# BM83.net
KiCad netlist of a schematic drawn in Altium Designer
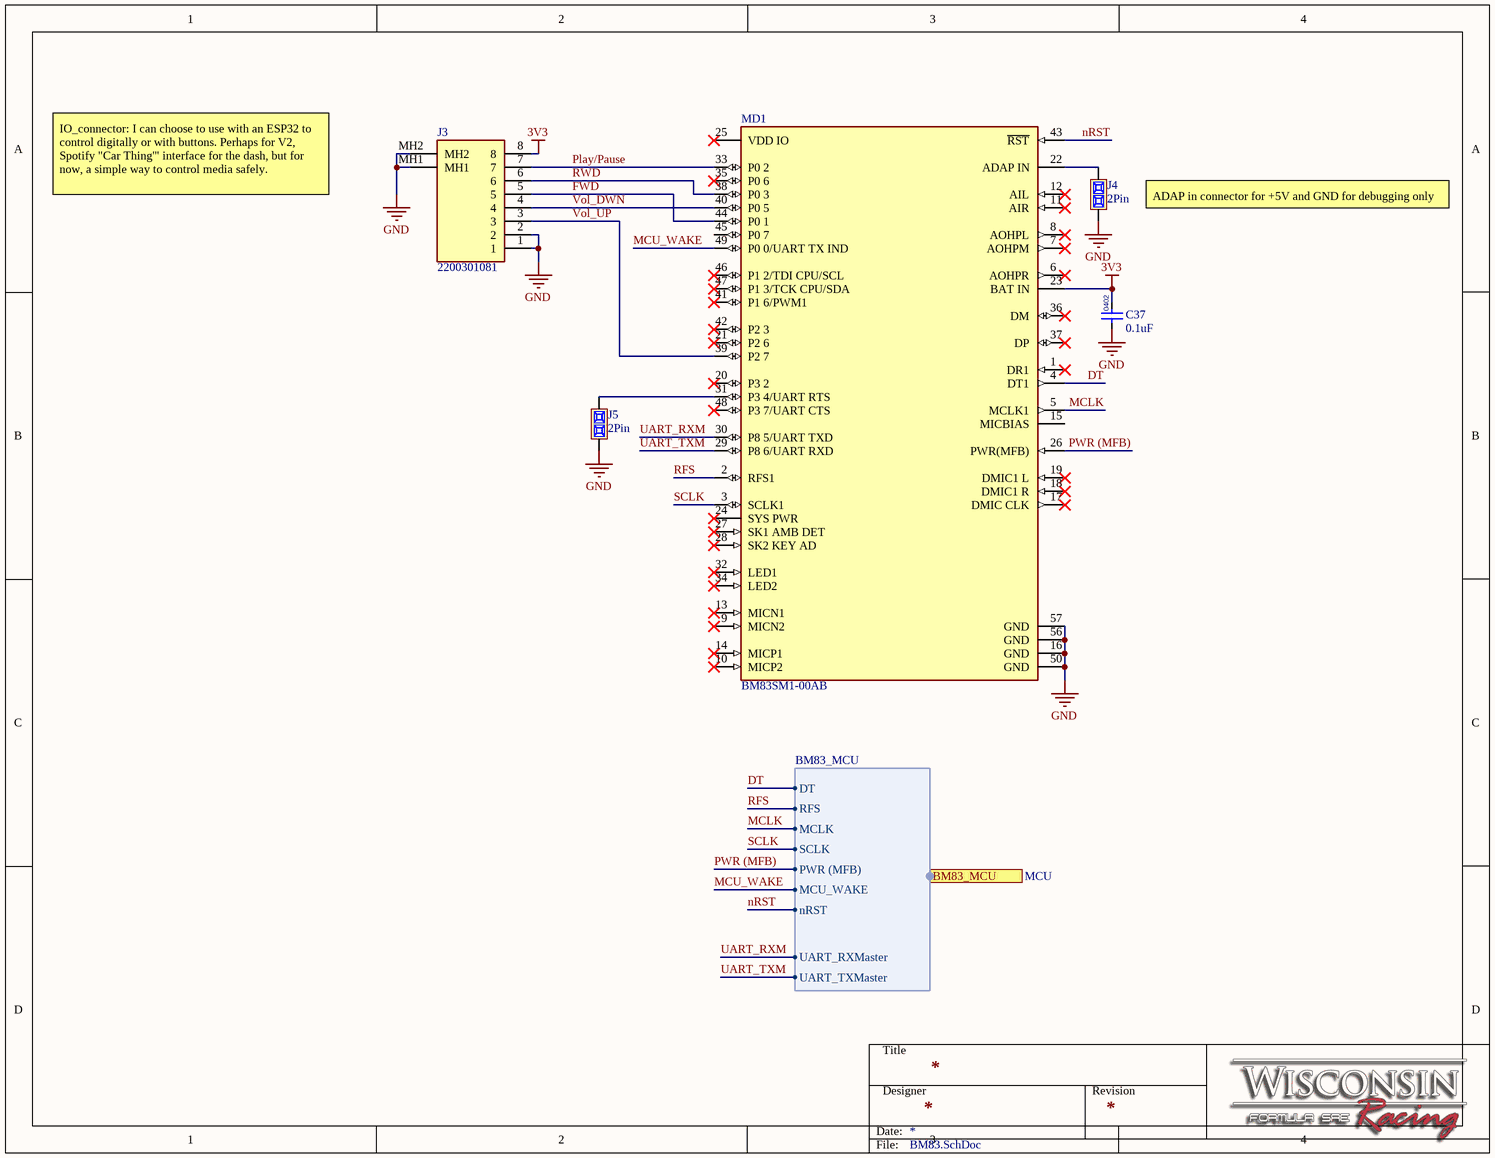
[diagram p0: BM83.SchDoc]

(export (version "E")
  (design (tool "Eeschema 10.0.6"))
  (components
    (comp (ref "C37")
      (value "0.1uF")
      (footprint "FP-CC0402-IPC_B")
      (fields (field (name "TOLERANCE") "10%"))
      (libsource (lib "University of Wisconsin Formula FSAE") (part "0402 ceramic cap"))
    )
    (comp (ref "J3")
      (value "2200301081")
      (footprint "SamacSys:2200301081")
      (description "Connector")
      (libsource (lib "*") (part "2200301081"))
    )
    (comp (ref "J4")
      (value "2Pin")
      (footprint "2 Pin Male")
      (libsource (lib "University of Wisconsin Formula FSAE") (part "2 Pin Male"))
    )
    (comp (ref "J5")
      (value "2Pin")
      (footprint "2 Pin Male")
      (libsource (lib "University of Wisconsin Formula FSAE") (part "2 Pin Male"))
    )
    (comp (ref "MD1")
      (value "BM83SM1-00AB")
      (footprint "FP-BM83SM1-00AB-MFG")
      (description "BLUETOOTH AUDIO MODULE")
      (libsource (lib "Altium Content Vault") (part "59273137af04f48cb9dd2df4763d70c"))
    )
  )
  (nets
    (net (code "2") (name "/DT") (class "Default")
      (node (ref "MD1") (pin "4") (pinfunction "DT1_4") (pintype "output"))
    )
    (net (code "3") (name "/FWD") (class "Default")
      (node (ref "J3") (pin "5") (pinfunction "5_5") (pintype "passive"))
      (node (ref "MD1") (pin "44") (pinfunction "P0_1_44") (pintype "bidirectional"))
    )
    (net (code "4") (name "/MCLK") (class "Default")
      (node (ref "MD1") (pin "5") (pinfunction "MCLK1_5") (pintype "output"))
    )
    (net (code "5") (name "/MCU_WAKE") (class "Default")
      (node (ref "MD1") (pin "49") (pinfunction "P0_0/UART_TX_IND_49") (pintype "bidirectional"))
    )
    (net (code "6") (name "/PWR (MFB)") (class "Default")
      (node (ref "MD1") (pin "26") (pinfunction "PWR(MFB)_26") (pintype "input"))
    )
    (net (code "7") (name "/Play{slash}Pause") (class "Default")
      (node (ref "J3") (pin "7") (pinfunction "7_7") (pintype "passive"))
      (node (ref "MD1") (pin "33") (pinfunction "P0_2_33") (pintype "bidirectional"))
    )
    (net (code "8") (name "/RFS") (class "Default")
      (node (ref "MD1") (pin "2") (pinfunction "RFS1_2") (pintype "bidirectional"))
    )
    (net (code "9") (name "/RWD") (class "Default")
      (node (ref "J3") (pin "6") (pinfunction "6_6") (pintype "passive"))
      (node (ref "MD1") (pin "38") (pinfunction "P0_3_38") (pintype "bidirectional"))
    )
    (net (code "10") (name "/SCLK") (class "Default")
      (node (ref "MD1") (pin "3") (pinfunction "SCLK1_3") (pintype "bidirectional"))
    )
    (net (code "11") (name "/UART_RXM") (class "Default")
      (node (ref "MD1") (pin "30") (pinfunction "P8_5/UART_TXD_30") (pintype "bidirectional"))
    )
    (net (code "12") (name "/UART_TXM") (class "Default")
      (node (ref "MD1") (pin "29") (pinfunction "P8_6/UART_RXD_29") (pintype "bidirectional"))
    )
    (net (code "13") (name "/Vol_DWN") (class "Default")
      (node (ref "J3") (pin "4") (pinfunction "4_4") (pintype "passive"))
      (node (ref "MD1") (pin "40") (pinfunction "P0_5_40") (pintype "bidirectional"))
    )
    (net (code "14") (name "/Vol_UP") (class "Default")
      (node (ref "J3") (pin "3") (pinfunction "3_3") (pintype "passive"))
      (node (ref "MD1") (pin "39") (pinfunction "P2_7_39") (pintype "bidirectional"))
    )
    (net (code "15") (name "/nRST") (class "Default")
      (node (ref "MD1") (pin "43") (pinfunction "~{RST}_43") (pintype "input"))
    )
    (net (code "17") (name "3V3") (class "Default")
      (node (ref "C37") (pin "2") (pinfunction "2_2") (pintype "passive"))
      (node (ref "J3") (pin "8") (pinfunction "8_8") (pintype "passive"))
      (node (ref "MD1") (pin "23") (pinfunction "BAT_IN_23") (pintype "power_in"))
    )
    (net (code "18") (name "GND") (class "Default")
      (node (ref "C37") (pin "1") (pinfunction "1_1") (pintype "passive"))
      (node (ref "J3") (pin "1") (pinfunction "1_1") (pintype "passive"))
      (node (ref "J3") (pin "2") (pinfunction "2_2") (pintype "passive"))
      (node (ref "J3") (pin "MH1") (pinfunction "MH1_MH1") (pintype "passive"))
      (node (ref "J3") (pin "MH2") (pinfunction "MH2_MH2") (pintype "passive"))
      (node (ref "J4") (pin "1") (pinfunction "1_1") (pintype "passive"))
      (node (ref "J5") (pin "1") (pinfunction "1_1") (pintype "passive"))
      (node (ref "MD1") (pin "16") (pinfunction "GND_16") (pintype "power_in"))
      (node (ref "MD1") (pin "50") (pinfunction "GND_50") (pintype "power_in"))
      (node (ref "MD1") (pin "56") (pinfunction "GND_56") (pintype "power_in"))
      (node (ref "MD1") (pin "57") (pinfunction "GND_57") (pintype "power_in"))
    )
    (net (code "19") (name "Net-(MD1-ADAP_IN)") (class "Default")
      (node (ref "J4") (pin "2") (pinfunction "2_2") (pintype "passive"))
      (node (ref "MD1") (pin "22") (pinfunction "ADAP_IN_22") (pintype "power_in"))
    )
    (net (code "20") (name "Net-(MD1-P3_4{slash}UART_RTS)") (class "Default")
      (node (ref "J5") (pin "2") (pinfunction "2_2") (pintype "passive"))
      (node (ref "MD1") (pin "31") (pinfunction "P3_4/UART_RTS_31") (pintype "bidirectional"))
    )
    (net (code "21") (name "unconnected-(MD1-AIL-Pad12)") (class "Default")
      (node (ref "MD1") (pin "12") (pinfunction "AIL_12") (pintype "input+no_connect"))
    )
    (net (code "22") (name "unconnected-(MD1-AIR-Pad11)") (class "Default")
      (node (ref "MD1") (pin "11") (pinfunction "AIR_11") (pintype "input+no_connect"))
    )
    (net (code "23") (name "unconnected-(MD1-AOHPL-Pad8)") (class "Default")
      (node (ref "MD1") (pin "8") (pinfunction "AOHPL_8") (pintype "output+no_connect"))
    )
    (net (code "24") (name "unconnected-(MD1-AOHPM-Pad7)") (class "Default")
      (node (ref "MD1") (pin "7") (pinfunction "AOHPM_7") (pintype "output+no_connect"))
    )
    (net (code "25") (name "unconnected-(MD1-AOHPR-Pad6)") (class "Default")
      (node (ref "MD1") (pin "6") (pinfunction "AOHPR_6") (pintype "output+no_connect"))
    )
    (net (code "26") (name "unconnected-(MD1-DM-Pad36)") (class "Default")
      (node (ref "MD1") (pin "36") (pinfunction "DM_36") (pintype "bidirectional+no_connect"))
    )
    (net (code "27") (name "unconnected-(MD1-DMIC1_L-Pad19)") (class "Default")
      (node (ref "MD1") (pin "19") (pinfunction "DMIC1_L_19") (pintype "input+no_connect"))
    )
    (net (code "28") (name "unconnected-(MD1-DMIC1_R-Pad18)") (class "Default")
      (node (ref "MD1") (pin "18") (pinfunction "DMIC1_R_18") (pintype "input+no_connect"))
    )
    (net (code "29") (name "unconnected-(MD1-DMIC_CLK-Pad17)") (class "Default")
      (node (ref "MD1") (pin "17") (pinfunction "DMIC_CLK_17") (pintype "output+no_connect"))
    )
    (net (code "30") (name "unconnected-(MD1-DP-Pad37)") (class "Default")
      (node (ref "MD1") (pin "37") (pinfunction "DP_37") (pintype "bidirectional+no_connect"))
    )
    (net (code "31") (name "unconnected-(MD1-DR1-Pad1)") (class "Default")
      (node (ref "MD1") (pin "1") (pinfunction "DR1_1") (pintype "input+no_connect"))
    )
    (net (code "32") (name "unconnected-(MD1-LED1-Pad32)") (class "Default")
      (node (ref "MD1") (pin "32") (pinfunction "LED1_32") (pintype "input+no_connect"))
    )
    (net (code "33") (name "unconnected-(MD1-LED2-Pad34)") (class "Default")
      (node (ref "MD1") (pin "34") (pinfunction "LED2_34") (pintype "input+no_connect"))
    )
    (net (code "34") (name "unconnected-(MD1-MICBIAS-Pad15)") (class "Default")
      (node (ref "MD1") (pin "15") (pinfunction "MICBIAS_15") (pintype "power_in"))
    )
    (net (code "35") (name "unconnected-(MD1-MICN1-Pad13)") (class "Default")
      (node (ref "MD1") (pin "13") (pinfunction "MICN1_13") (pintype "input+no_connect"))
    )
    (net (code "36") (name "unconnected-(MD1-MICN2-Pad9)") (class "Default")
      (node (ref "MD1") (pin "9") (pinfunction "MICN2_9") (pintype "input+no_connect"))
    )
    (net (code "37") (name "unconnected-(MD1-MICP1-Pad14)") (class "Default")
      (node (ref "MD1") (pin "14") (pinfunction "MICP1_14") (pintype "input+no_connect"))
    )
    (net (code "38") (name "unconnected-(MD1-MICP2-Pad10)") (class "Default")
      (node (ref "MD1") (pin "10") (pinfunction "MICP2_10") (pintype "input+no_connect"))
    )
    (net (code "39") (name "unconnected-(MD1-P0_6-Pad35)") (class "Default")
      (node (ref "MD1") (pin "35") (pinfunction "P0_6_35") (pintype "bidirectional+no_connect"))
    )
    (net (code "40") (name "unconnected-(MD1-P0_7-Pad45)") (class "Default")
      (node (ref "MD1") (pin "45") (pinfunction "P0_7_45") (pintype "bidirectional"))
    )
    (net (code "41") (name "unconnected-(MD1-P1_2{slash}TDI_CPU{slash}SCL-Pad46)") (class "Default")
      (node (ref "MD1") (pin "46") (pinfunction "P1_2/TDI_CPU/SCL_46") (pintype "bidirectional+no_connect"))
    )
    (net (code "42") (name "unconnected-(MD1-P1_3{slash}TCK_CPU{slash}SDA-Pad47)") (class "Default")
      (node (ref "MD1") (pin "47") (pinfunction "P1_3/TCK_CPU/SDA_47") (pintype "bidirectional+no_connect"))
    )
    (net (code "43") (name "unconnected-(MD1-P1_6{slash}PWM1-Pad41)") (class "Default")
      (node (ref "MD1") (pin "41") (pinfunction "P1_6/PWM1_41") (pintype "bidirectional+no_connect"))
    )
    (net (code "44") (name "unconnected-(MD1-P2_3-Pad42)") (class "Default")
      (node (ref "MD1") (pin "42") (pinfunction "P2_3_42") (pintype "bidirectional+no_connect"))
    )
    (net (code "45") (name "unconnected-(MD1-P2_6-Pad21)") (class "Default")
      (node (ref "MD1") (pin "21") (pinfunction "P2_6_21") (pintype "bidirectional+no_connect"))
    )
    (net (code "46") (name "unconnected-(MD1-P3_2-Pad20)") (class "Default")
      (node (ref "MD1") (pin "20") (pinfunction "P3_2_20") (pintype "bidirectional+no_connect"))
    )
    (net (code "47") (name "unconnected-(MD1-P3_7{slash}UART_CTS-Pad48)") (class "Default")
      (node (ref "MD1") (pin "48") (pinfunction "P3_7/UART_CTS_48") (pintype "bidirectional+no_connect"))
    )
    (net (code "48") (name "unconnected-(MD1-SK1_AMB_DET-Pad27)") (class "Default")
      (node (ref "MD1") (pin "27") (pinfunction "SK1_AMB_DET_27") (pintype "input+no_connect"))
    )
    (net (code "49") (name "unconnected-(MD1-SK2_KEY_AD-Pad28)") (class "Default")
      (node (ref "MD1") (pin "28") (pinfunction "SK2_KEY_AD_28") (pintype "input+no_connect"))
    )
    (net (code "50") (name "unconnected-(MD1-SYS_PWR-Pad24)") (class "Default")
      (node (ref "MD1") (pin "24") (pinfunction "SYS_PWR_24") (pintype "power_in+no_connect"))
    )
    (net (code "51") (name "unconnected-(MD1-VDD_IO-Pad25)") (class "Default")
      (node (ref "MD1") (pin "25") (pinfunction "VDD_IO_25") (pintype "power_in+no_connect"))
    )
  )
)
